# Schematico.net
KiCad netlist of a schematic drawn in EAGLE
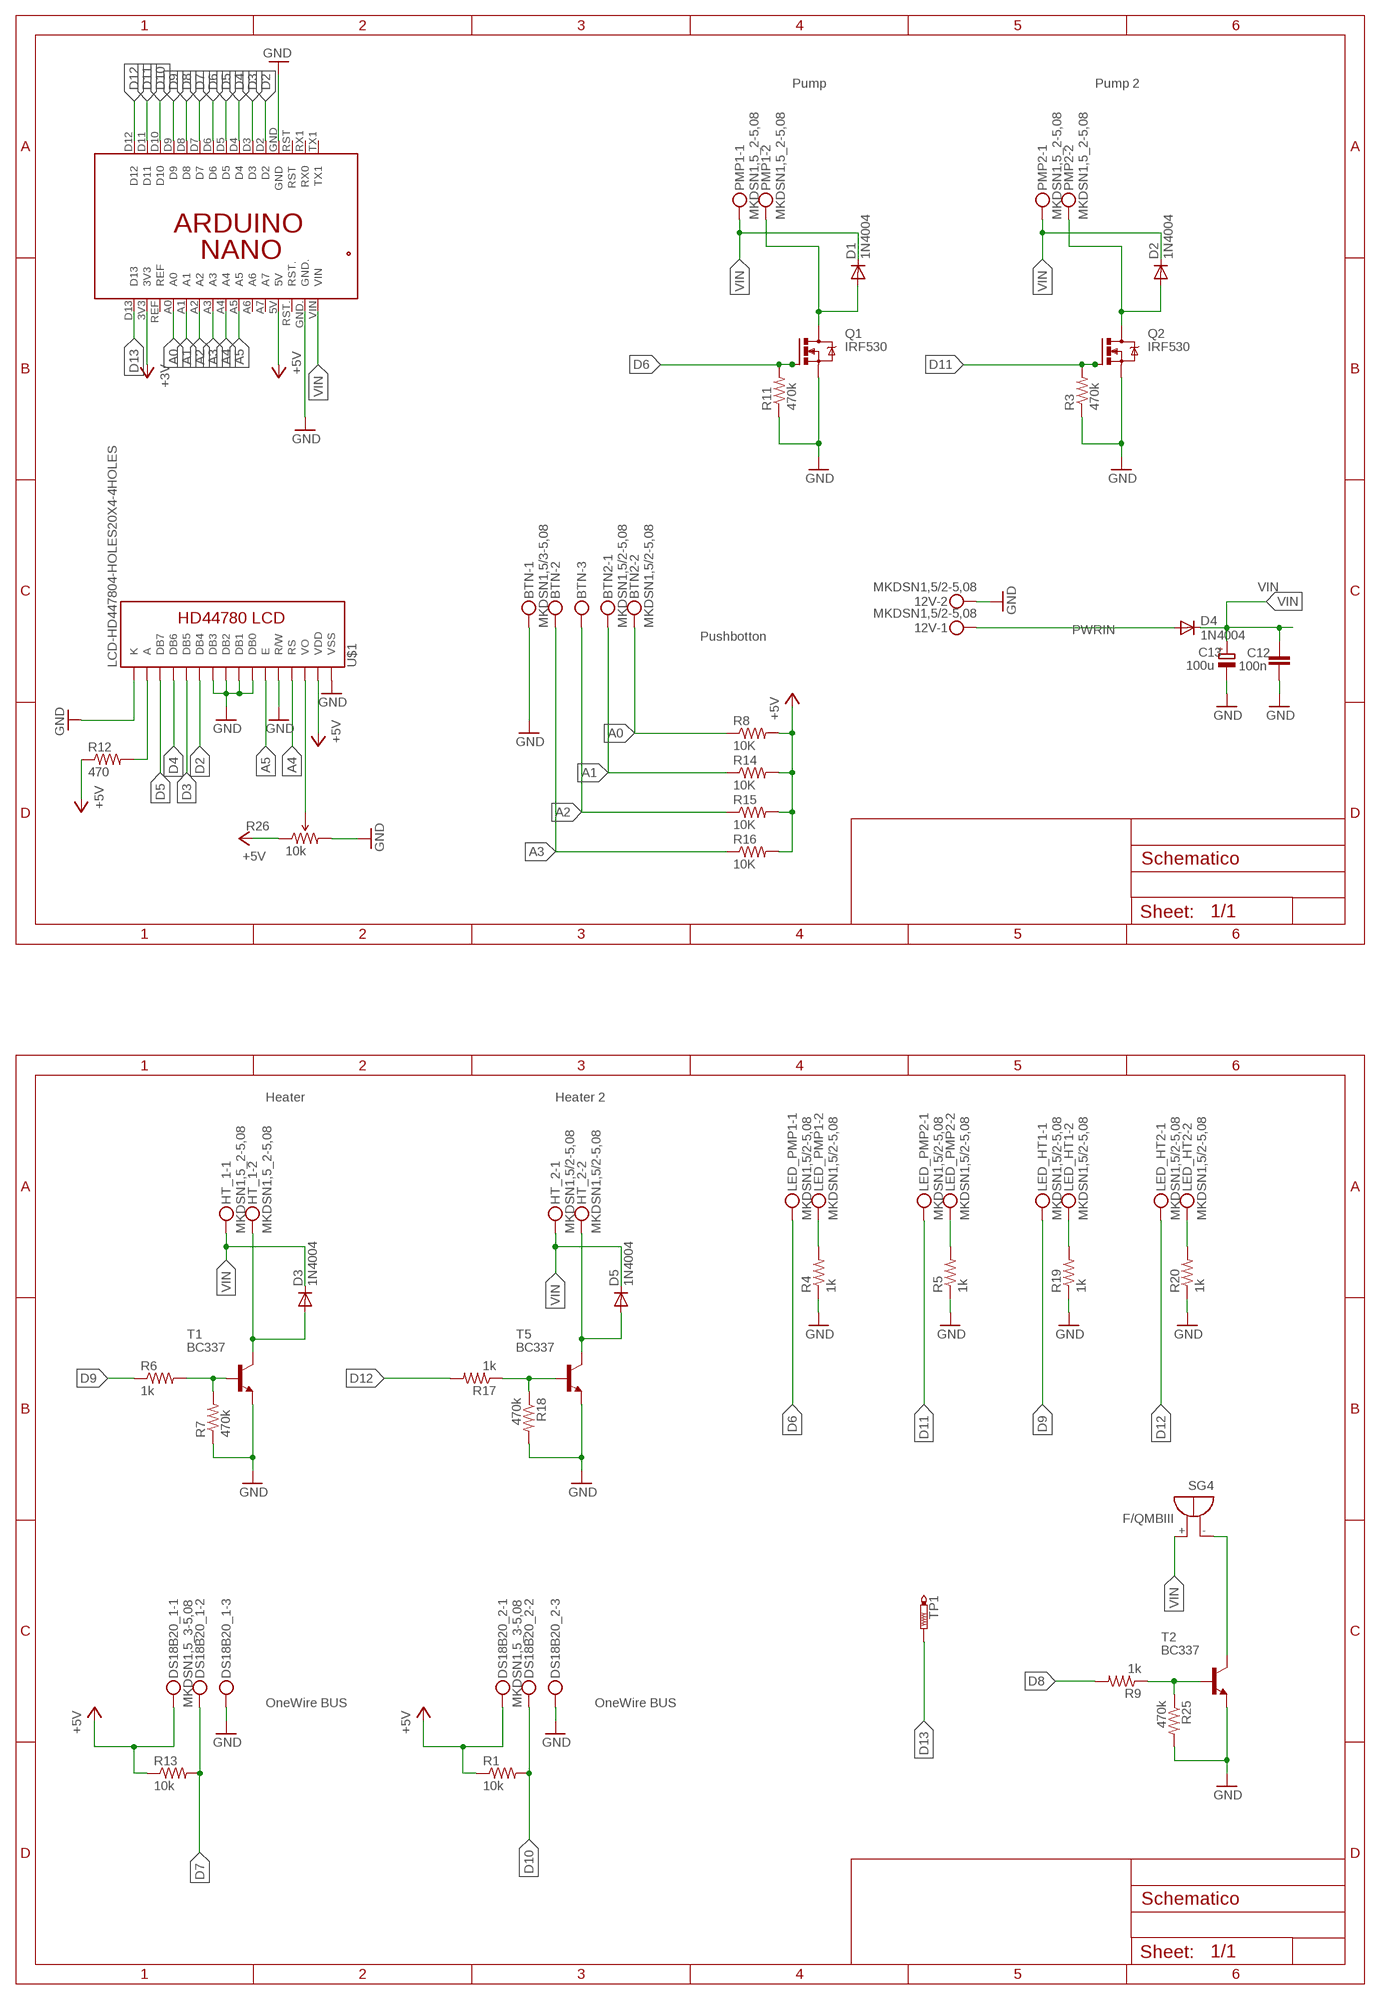
[diagram p0: schematic, sheet 1]

(export (version "E")
  (design (tool "Eeschema 10.0.6"))
  (components
    (comp (ref "12V")
      (value "MKDSN1,5/2-5,08")
      (footprint "eagle-import:MKDSN1,5_2-5,08")
      (fields (field (name "OC_NEWARK") "unknown"))
      (libsource (lib "eagle-import") (part "MKDSN1,5/2-5,08"))
    )
    (comp (ref "BTN")
      (value "MKDSN1,5/3-5,08")
      (footprint "eagle-import:MKDSN1,5_3-5,08")
      (fields (field (name "OC_NEWARK") "unknown"))
      (libsource (lib "eagle-import") (part "MKDSN1,5/3-5,08"))
    )
    (comp (ref "BTN2")
      (value "MKDSN1,5/2-5,08")
      (footprint "eagle-import:MKDSN1,5_2-5,08")
      (fields (field (name "OC_NEWARK") "unknown"))
      (libsource (lib "eagle-import") (part "MKDSN1,5/2-5,08"))
    )
    (comp (ref "C12")
      (value "100n")
      (footprint "eagle-import:C050-024X044")
      (libsource (lib "eagle-import") (part "C-EU050-024X044"))
    )
    (comp (ref "C13")
      (value "100u")
      (footprint "eagle-import:TT5D6")
      (libsource (lib "eagle-import") (part "CPOL-EUTT6D6"))
    )
    (comp (ref "D1")
      (value "1N4004")
      (footprint "eagle-import:DO41-10")
      (libsource (lib "eagle-import") (part "1N4004"))
    )
    (comp (ref "D2")
      (value "1N4004")
      (footprint "eagle-import:DO41-10")
      (libsource (lib "eagle-import") (part "1N4004"))
    )
    (comp (ref "D3")
      (value "1N4004")
      (footprint "eagle-import:DO41-10")
      (libsource (lib "eagle-import") (part "1N4004"))
    )
    (comp (ref "D4")
      (value "1N4004")
      (footprint "eagle-import:DO41-10")
      (libsource (lib "eagle-import") (part "1N4004"))
    )
    (comp (ref "D5")
      (value "1N4004")
      (footprint "eagle-import:DO41-10")
      (libsource (lib "eagle-import") (part "1N4004"))
    )
    (comp (ref "DS18B20_1")
      (value "MKDSN1,5_3-5,08")
      (footprint "eagle-import:MKDSN1,5-3-5,08")
      (fields (field (name "OC_NEWARK") "unknown"))
      (libsource (lib "eagle-import") (part "MKDSN1,5_3-5,08"))
    )
    (comp (ref "DS18B20_2")
      (value "MKDSN1,5_3-5,08")
      (footprint "eagle-import:MKDSN1,5-3-5,08")
      (fields (field (name "OC_NEWARK") "unknown"))
      (libsource (lib "eagle-import") (part "MKDSN1,5_3-5,08"))
    )
    (comp (ref "HT_1")
      (value "MKDSN1,5_2-5,08")
      (footprint "eagle-import:MKDSN1,5-2-5,08")
      (fields (field (name "OC_NEWARK") "unknown"))
      (libsource (lib "eagle-import") (part "MKDSN1,5_2-5,08"))
    )
    (comp (ref "HT_2")
      (value "MKDSN1,5/2-5,08")
      (footprint "eagle-import:MKDSN1,5_2-5,08")
      (libsource (lib "eagle-import") (part "MKDSN1,5/2-5,08"))
    )
    (comp (ref "LED_HT1")
      (value "MKDSN1,5/2-5,08")
      (footprint "eagle-import:MKDSN1,5_2-5,08")
      (libsource (lib "eagle-import") (part "MKDSN1,5/2-5,08"))
    )
    (comp (ref "LED_HT2")
      (value "MKDSN1,5/2-5,08")
      (footprint "eagle-import:MKDSN1,5_2-5,08")
      (libsource (lib "eagle-import") (part "MKDSN1,5/2-5,08"))
    )
    (comp (ref "LED_PMP1")
      (value "MKDSN1,5/2-5,08")
      (footprint "eagle-import:MKDSN1,5_2-5,08")
      (libsource (lib "eagle-import") (part "MKDSN1,5/2-5,08"))
    )
    (comp (ref "LED_PMP2")
      (value "MKDSN1,5/2-5,08")
      (footprint "eagle-import:MKDSN1,5_2-5,08")
      (libsource (lib "eagle-import") (part "MKDSN1,5/2-5,08"))
    )
    (comp (ref "PCB1")
      (value "ARDUINO_NANO")
      (footprint "eagle-import:ARDUINO_NANO")
      (libsource (lib "eagle-import") (part "ARDUINO_NANO"))
    )
    (comp (ref "PMP1")
      (value "MKDSN1,5_2-5,08")
      (footprint "eagle-import:MKDSN1,5-2-5,08")
      (fields (field (name "OC_NEWARK") "unknown"))
      (libsource (lib "eagle-import") (part "MKDSN1,5_2-5,08"))
    )
    (comp (ref "PMP2")
      (value "MKDSN1,5_2-5,08")
      (footprint "eagle-import:MKDSN1,5-2-5,08")
      (fields (field (name "OC_NEWARK") "unknown"))
      (libsource (lib "eagle-import") (part "MKDSN1,5_2-5,08"))
    )
    (comp (ref "Q1")
      (value "IRF530")
      (footprint "eagle-import:TO220BV")
      (libsource (lib "eagle-import") (part "IRF530"))
    )
    (comp (ref "Q2")
      (value "IRF530")
      (footprint "eagle-import:TO220BV")
      (libsource (lib "eagle-import") (part "IRF530"))
    )
    (comp (ref "R1")
      (value "10k")
      (footprint "eagle-import:0207_10")
      (libsource (lib "eagle-import") (part "R-US_0207/10"))
    )
    (comp (ref "R3")
      (value "470k")
      (footprint "eagle-import:0207_10")
      (libsource (lib "eagle-import") (part "R-US_0207/10"))
    )
    (comp (ref "R4")
      (value "1k")
      (footprint "eagle-import:0207_10")
      (libsource (lib "eagle-import") (part "R-US_0207/10"))
    )
    (comp (ref "R5")
      (value "1k")
      (footprint "eagle-import:0207_10")
      (libsource (lib "eagle-import") (part "R-US_0207/10"))
    )
    (comp (ref "R6")
      (value "1k")
      (footprint "eagle-import:0207_10")
      (libsource (lib "eagle-import") (part "R-US_0207/10"))
    )
    (comp (ref "R7")
      (value "470k")
      (footprint "eagle-import:0207_10")
      (libsource (lib "eagle-import") (part "R-US_0207/10"))
    )
    (comp (ref "R8")
      (value "10K")
      (footprint "eagle-import:0207_10")
      (libsource (lib "eagle-import") (part "R-US_0207/10"))
    )
    (comp (ref "R9")
      (value "1k")
      (footprint "eagle-import:0207_10")
      (libsource (lib "eagle-import") (part "R-US_0207/10"))
    )
    (comp (ref "R11")
      (value "470k")
      (footprint "eagle-import:0207_10")
      (libsource (lib "eagle-import") (part "R-US_0207/10"))
    )
    (comp (ref "R12")
      (value "470")
      (footprint "eagle-import:0207_10")
      (libsource (lib "eagle-import") (part "R-US_0207/10"))
    )
    (comp (ref "R13")
      (value "10k")
      (footprint "eagle-import:0207_10")
      (libsource (lib "eagle-import") (part "R-US_0207/10"))
    )
    (comp (ref "R14")
      (value "10K")
      (footprint "eagle-import:0207_10")
      (libsource (lib "eagle-import") (part "R-US_0207/10"))
    )
    (comp (ref "R15")
      (value "10K")
      (footprint "eagle-import:0207_10")
      (libsource (lib "eagle-import") (part "R-US_0207/10"))
    )
    (comp (ref "R16")
      (value "10K")
      (footprint "eagle-import:0207_10")
      (libsource (lib "eagle-import") (part "R-US_0207/10"))
    )
    (comp (ref "R17")
      (value "1k")
      (footprint "eagle-import:0207_10")
      (libsource (lib "eagle-import") (part "R-US_0207/10"))
    )
    (comp (ref "R18")
      (value "470k")
      (footprint "eagle-import:0207_10")
      (libsource (lib "eagle-import") (part "R-US_0207/10"))
    )
    (comp (ref "R19")
      (value "1k")
      (footprint "eagle-import:0207_10")
      (libsource (lib "eagle-import") (part "R-US_0207/10"))
    )
    (comp (ref "R20")
      (value "1k")
      (footprint "eagle-import:0207_10")
      (libsource (lib "eagle-import") (part "R-US_0207/10"))
    )
    (comp (ref "R25")
      (value "470k")
      (footprint "eagle-import:0207_10")
      (libsource (lib "eagle-import") (part "R-US_0207/10"))
    )
    (comp (ref "R26")
      (value "10k")
      (footprint "eagle-import:3362U-2")
      (libsource (lib "eagle-import") (part "TRIMPOT3362U-2"))
    )
    (comp (ref "SG4")
      (value "F/QMBIII")
      (footprint "eagle-import:F_QMBIII")
      (libsource (lib "eagle-import") (part "F/QMBIII"))
    )
    (comp (ref "T1")
      (value "BC337")
      (footprint "eagle-import:TO92")
      (libsource (lib "eagle-import") (part "BC337"))
    )
    (comp (ref "T2")
      (value "BC337")
      (footprint "eagle-import:TO92")
      (libsource (lib "eagle-import") (part "BC337"))
    )
    (comp (ref "T5")
      (value "BC337")
      (footprint "eagle-import:TO92")
      (libsource (lib "eagle-import") (part "BC337"))
    )
    (comp (ref "TP1")
      (value "PTR1PAD1-20")
      (footprint "eagle-import:P1-20")
      (libsource (lib "eagle-import") (part "PTR1PAD1-20"))
    )
    (comp (ref "U$1")
      (value "LCD-HD447804-HOLES20X4-4HOLES")
      (footprint "eagle-import:LCD-20X4-4HOLES")
      (libsource (lib "eagle-import") (part "LCD-HD4478020X4-4HOLES4-HOLES"))
    )
  )
  (nets
    (net (code "1") (name "+3V") (class "Default")
      (node (ref "PCB1") (pin "3V3") (pinfunction "3V3_3V3") (pintype "bidirectional"))
    )
    (net (code "2") (name "+5V") (class "Default")
      (node (ref "DS18B20_1") (pin "1") (pinfunction "KL_1") (pintype "passive"))
      (node (ref "DS18B20_2") (pin "1") (pinfunction "KL_1") (pintype "passive"))
      (node (ref "PCB1") (pin "5V") (pinfunction "5V_5V") (pintype "bidirectional"))
      (node (ref "R1") (pin "1") (pinfunction "1_1") (pintype "passive"))
      (node (ref "R12") (pin "1") (pinfunction "1_1") (pintype "passive"))
      (node (ref "R13") (pin "1") (pinfunction "1_1") (pintype "passive"))
      (node (ref "R14") (pin "2") (pinfunction "2_2") (pintype "passive"))
      (node (ref "R15") (pin "2") (pinfunction "2_2") (pintype "passive"))
      (node (ref "R16") (pin "2") (pinfunction "2_2") (pintype "passive"))
      (node (ref "R26") (pin "1") (pinfunction "CCW_1") (pintype "passive"))
      (node (ref "R8") (pin "2") (pinfunction "2_2") (pintype "passive"))
      (node (ref "U$1") (pin "P$2") (pinfunction "VDD_P$2") (pintype "power_in"))
    )
    (net (code "3") (name "/PWRIN") (class "Default")
      (node (ref "12V") (pin "1") (pinfunction "KL_1") (pintype "passive"))
      (node (ref "D4") (pin "A") (pinfunction "A_A") (pintype "passive"))
    )
    (net (code "4") (name "A0") (class "Default")
      (node (ref "BTN2") (pin "2") (pinfunction "KL_2") (pintype "passive"))
      (node (ref "PCB1") (pin "A0") (pinfunction "A0_A0") (pintype "bidirectional"))
      (node (ref "R8") (pin "1") (pinfunction "1_1") (pintype "passive"))
    )
    (net (code "5") (name "A1") (class "Default")
      (node (ref "BTN2") (pin "1") (pinfunction "KL_1") (pintype "passive"))
      (node (ref "PCB1") (pin "A1") (pinfunction "A1_A1") (pintype "bidirectional"))
      (node (ref "R14") (pin "1") (pinfunction "1_1") (pintype "passive"))
    )
    (net (code "6") (name "A2") (class "Default")
      (node (ref "BTN") (pin "3") (pinfunction "KL_3") (pintype "passive"))
      (node (ref "PCB1") (pin "A2") (pinfunction "A2_A2") (pintype "bidirectional"))
      (node (ref "R15") (pin "1") (pinfunction "1_1") (pintype "passive"))
    )
    (net (code "7") (name "A3") (class "Default")
      (node (ref "BTN") (pin "2") (pinfunction "KL_2") (pintype "passive"))
      (node (ref "PCB1") (pin "A3") (pinfunction "A3_A3") (pintype "bidirectional"))
      (node (ref "R16") (pin "1") (pinfunction "1_1") (pintype "passive"))
    )
    (net (code "8") (name "A4") (class "Default")
      (node (ref "PCB1") (pin "A4") (pinfunction "A4_A4") (pintype "bidirectional"))
      (node (ref "U$1") (pin "P$4") (pinfunction "RS_P$4") (pintype "input"))
    )
    (net (code "9") (name "A5") (class "Default")
      (node (ref "PCB1") (pin "A5") (pinfunction "A5_A5") (pintype "bidirectional"))
      (node (ref "U$1") (pin "P$6") (pinfunction "E_P$6") (pintype "input"))
    )
    (net (code "10") (name "D2") (class "Default")
      (node (ref "PCB1") (pin "D2") (pinfunction "D2_D2") (pintype "bidirectional"))
      (node (ref "U$1") (pin "P$11") (pinfunction "DB4_P$11") (pintype "bidirectional"))
    )
    (net (code "11") (name "D3") (class "Default")
      (node (ref "PCB1") (pin "D3") (pinfunction "D3_D3") (pintype "bidirectional"))
      (node (ref "U$1") (pin "P$12") (pinfunction "DB5_P$12") (pintype "bidirectional"))
    )
    (net (code "12") (name "D4") (class "Default")
      (node (ref "PCB1") (pin "D4") (pinfunction "D4_D4") (pintype "bidirectional"))
      (node (ref "U$1") (pin "P$13") (pinfunction "DB6_P$13") (pintype "bidirectional"))
    )
    (net (code "13") (name "D5") (class "Default")
      (node (ref "PCB1") (pin "D5") (pinfunction "D5_D5") (pintype "bidirectional"))
      (node (ref "U$1") (pin "P$14") (pinfunction "DB7_P$14") (pintype "bidirectional"))
    )
    (net (code "14") (name "D6") (class "Default")
      (node (ref "LED_PMP1") (pin "1") (pinfunction "KL_1") (pintype "passive"))
      (node (ref "PCB1") (pin "D6") (pinfunction "D6_D6") (pintype "bidirectional"))
      (node (ref "Q1") (pin "G") (pinfunction "G_G") (pintype "passive"))
      (node (ref "R11") (pin "2") (pinfunction "2_2") (pintype "passive"))
    )
    (net (code "15") (name "D7") (class "Default")
      (node (ref "DS18B20_1") (pin "2") (pinfunction "KL_2") (pintype "passive"))
      (node (ref "PCB1") (pin "D7") (pinfunction "D7_D7") (pintype "bidirectional"))
      (node (ref "R13") (pin "2") (pinfunction "2_2") (pintype "passive"))
    )
    (net (code "16") (name "D8") (class "Default")
      (node (ref "PCB1") (pin "D8") (pinfunction "D8_D8") (pintype "bidirectional"))
      (node (ref "R9") (pin "2") (pinfunction "2_2") (pintype "passive"))
    )
    (net (code "17") (name "D9") (class "Default")
      (node (ref "LED_HT1") (pin "1") (pinfunction "KL_1") (pintype "passive"))
      (node (ref "PCB1") (pin "D9") (pinfunction "D9_D9") (pintype "bidirectional"))
      (node (ref "R6") (pin "1") (pinfunction "1_1") (pintype "passive"))
    )
    (net (code "18") (name "D10") (class "Default")
      (node (ref "DS18B20_2") (pin "2") (pinfunction "KL_2") (pintype "passive"))
      (node (ref "PCB1") (pin "D10") (pinfunction "D10_D10") (pintype "bidirectional"))
      (node (ref "R1") (pin "2") (pinfunction "2_2") (pintype "passive"))
    )
    (net (code "19") (name "D11") (class "Default")
      (node (ref "LED_PMP2") (pin "1") (pinfunction "KL_1") (pintype "passive"))
      (node (ref "PCB1") (pin "D11") (pinfunction "D11_D11") (pintype "bidirectional"))
      (node (ref "Q2") (pin "G") (pinfunction "G_G") (pintype "passive"))
      (node (ref "R3") (pin "2") (pinfunction "2_2") (pintype "passive"))
    )
    (net (code "20") (name "D12") (class "Default")
      (node (ref "LED_HT2") (pin "1") (pinfunction "KL_1") (pintype "passive"))
      (node (ref "PCB1") (pin "D12") (pinfunction "D12_D12") (pintype "bidirectional"))
      (node (ref "R17") (pin "2") (pinfunction "2_2") (pintype "passive"))
    )
    (net (code "21") (name "D13") (class "Default")
      (node (ref "PCB1") (pin "D13") (pinfunction "D13_D13") (pintype "bidirectional"))
      (node (ref "TP1") (pin "TP") (pinfunction "TP_TP") (pintype "input"))
    )
    (net (code "22") (name "GND") (class "Default")
      (node (ref "12V") (pin "2") (pinfunction "KL_2") (pintype "passive"))
      (node (ref "BTN") (pin "1") (pinfunction "KL_1") (pintype "passive"))
      (node (ref "C12") (pin "1") (pinfunction "1_1") (pintype "passive"))
      (node (ref "C13") (pin "-") (pinfunction "-_-") (pintype "passive"))
      (node (ref "DS18B20_1") (pin "3") (pinfunction "KL_3") (pintype "passive"))
      (node (ref "DS18B20_2") (pin "3") (pinfunction "KL_3") (pintype "passive"))
      (node (ref "PCB1") (pin "GND") (pinfunction "GND_GND") (pintype "bidirectional"))
      (node (ref "PCB1") (pin "GND.") (pinfunction "GND._GND.") (pintype "bidirectional"))
      (node (ref "Q1") (pin "S") (pinfunction "S_S") (pintype "passive"))
      (node (ref "Q2") (pin "S") (pinfunction "S_S") (pintype "passive"))
      (node (ref "R11") (pin "1") (pinfunction "1_1") (pintype "passive"))
      (node (ref "R18") (pin "2") (pinfunction "2_2") (pintype "passive"))
      (node (ref "R19") (pin "1") (pinfunction "1_1") (pintype "passive"))
      (node (ref "R20") (pin "1") (pinfunction "1_1") (pintype "passive"))
      (node (ref "R25") (pin "2") (pinfunction "2_2") (pintype "passive"))
      (node (ref "R26") (pin "3") (pinfunction "CW_3") (pintype "passive"))
      (node (ref "R3") (pin "1") (pinfunction "1_1") (pintype "passive"))
      (node (ref "R4") (pin "1") (pinfunction "1_1") (pintype "passive"))
      (node (ref "R5") (pin "1") (pinfunction "1_1") (pintype "passive"))
      (node (ref "R7") (pin "1") (pinfunction "1_1") (pintype "passive"))
      (node (ref "T1") (pin "1") (pinfunction "E_1") (pintype "passive"))
      (node (ref "T2") (pin "1") (pinfunction "E_1") (pintype "passive"))
      (node (ref "T5") (pin "1") (pinfunction "E_1") (pintype "passive"))
      (node (ref "U$1") (pin "P$1") (pinfunction "VSS_P$1") (pintype "power_in"))
      (node (ref "U$1") (pin "P$10") (pinfunction "DB3_P$10") (pintype "bidirectional"))
      (node (ref "U$1") (pin "P$16") (pinfunction "K_P$16") (pintype "power_in"))
      (node (ref "U$1") (pin "P$5") (pinfunction "R/W_P$5") (pintype "input"))
      (node (ref "U$1") (pin "P$7") (pinfunction "DB0_P$7") (pintype "bidirectional"))
      (node (ref "U$1") (pin "P$8") (pinfunction "DB1_P$8") (pintype "bidirectional"))
      (node (ref "U$1") (pin "P$9") (pinfunction "DB2_P$9") (pintype "bidirectional"))
    )
    (net (code "23") (name "Net-(HT_1B-KL)") (class "Default")
      (node (ref "D3") (pin "A") (pinfunction "A_A") (pintype "passive"))
      (node (ref "HT_1") (pin "2") (pinfunction "KL_2") (pintype "passive"))
      (node (ref "T1") (pin "3") (pinfunction "C_3") (pintype "passive"))
    )
    (net (code "24") (name "Net-(HT_2B-KL)") (class "Default")
      (node (ref "D5") (pin "A") (pinfunction "A_A") (pintype "passive"))
      (node (ref "HT_2") (pin "2") (pinfunction "KL_2") (pintype "passive"))
      (node (ref "T5") (pin "3") (pinfunction "C_3") (pintype "passive"))
    )
    (net (code "25") (name "Net-(LED_HT1B-KL)") (class "Default")
      (node (ref "LED_HT1") (pin "2") (pinfunction "KL_2") (pintype "passive"))
      (node (ref "R19") (pin "2") (pinfunction "2_2") (pintype "passive"))
    )
    (net (code "26") (name "Net-(LED_HT2B-KL)") (class "Default")
      (node (ref "LED_HT2") (pin "2") (pinfunction "KL_2") (pintype "passive"))
      (node (ref "R20") (pin "2") (pinfunction "2_2") (pintype "passive"))
    )
    (net (code "27") (name "Net-(LED_PMP1B-KL)") (class "Default")
      (node (ref "LED_PMP1") (pin "2") (pinfunction "KL_2") (pintype "passive"))
      (node (ref "R4") (pin "2") (pinfunction "2_2") (pintype "passive"))
    )
    (net (code "28") (name "Net-(LED_PMP2B-KL)") (class "Default")
      (node (ref "LED_PMP2") (pin "2") (pinfunction "KL_2") (pintype "passive"))
      (node (ref "R5") (pin "2") (pinfunction "2_2") (pintype "passive"))
    )
    (net (code "29") (name "Net-(PMP1B-KL)") (class "Default")
      (node (ref "D1") (pin "A") (pinfunction "A_A") (pintype "passive"))
      (node (ref "PMP1") (pin "2") (pinfunction "KL_2") (pintype "passive"))
      (node (ref "Q1") (pin "D") (pinfunction "D_D") (pintype "passive"))
    )
    (net (code "30") (name "Net-(PMP2B-KL)") (class "Default")
      (node (ref "D2") (pin "A") (pinfunction "A_A") (pintype "passive"))
      (node (ref "PMP2") (pin "2") (pinfunction "KL_2") (pintype "passive"))
      (node (ref "Q2") (pin "D") (pinfunction "D_D") (pintype "passive"))
    )
    (net (code "31") (name "Net-(R26-WIPER)") (class "Default")
      (node (ref "R26") (pin "2") (pinfunction "WIPER_2") (pintype "passive"))
      (node (ref "U$1") (pin "P$3") (pinfunction "VO_P$3") (pintype "bidirectional"))
    )
    (net (code "32") (name "Net-(SG4-+)") (class "Default")
      (node (ref "SG4") (pin "-") (pinfunction "+_-") (pintype "passive"))
      (node (ref "T2") (pin "3") (pinfunction "C_3") (pintype "passive"))
    )
    (net (code "33") (name "Net-(T1-B)") (class "Default")
      (node (ref "R6") (pin "2") (pinfunction "2_2") (pintype "passive"))
      (node (ref "R7") (pin "2") (pinfunction "2_2") (pintype "passive"))
      (node (ref "T1") (pin "2") (pinfunction "B_2") (pintype "passive"))
    )
    (net (code "34") (name "Net-(T2-B)") (class "Default")
      (node (ref "R25") (pin "1") (pinfunction "1_1") (pintype "passive"))
      (node (ref "R9") (pin "1") (pinfunction "1_1") (pintype "passive"))
      (node (ref "T2") (pin "2") (pinfunction "B_2") (pintype "passive"))
    )
    (net (code "35") (name "Net-(T5-B)") (class "Default")
      (node (ref "R17") (pin "1") (pinfunction "1_1") (pintype "passive"))
      (node (ref "R18") (pin "1") (pinfunction "1_1") (pintype "passive"))
      (node (ref "T5") (pin "2") (pinfunction "B_2") (pintype "passive"))
    )
    (net (code "36") (name "Net-(U$1-A)") (class "Default")
      (node (ref "R12") (pin "2") (pinfunction "2_2") (pintype "passive"))
      (node (ref "U$1") (pin "P$15") (pinfunction "A_P$15") (pintype "power_in"))
    )
    (net (code "37") (name "VIN") (class "Default")
      (node (ref "C12") (pin "2") (pinfunction "2_2") (pintype "passive"))
      (node (ref "C13") (pin "+") (pinfunction "+_+") (pintype "passive"))
      (node (ref "D1") (pin "C") (pinfunction "C_C") (pintype "passive"))
      (node (ref "D2") (pin "C") (pinfunction "C_C") (pintype "passive"))
      (node (ref "D3") (pin "C") (pinfunction "C_C") (pintype "passive"))
      (node (ref "D4") (pin "C") (pinfunction "C_C") (pintype "passive"))
      (node (ref "D5") (pin "C") (pinfunction "C_C") (pintype "passive"))
      (node (ref "HT_1") (pin "1") (pinfunction "KL_1") (pintype "passive"))
      (node (ref "HT_2") (pin "1") (pinfunction "KL_1") (pintype "passive"))
      (node (ref "PCB1") (pin "VIN") (pinfunction "VIN_VIN") (pintype "bidirectional"))
      (node (ref "PMP1") (pin "1") (pinfunction "KL_1") (pintype "passive"))
      (node (ref "PMP2") (pin "1") (pinfunction "KL_1") (pintype "passive"))
      (node (ref "SG4") (pin "+") (pinfunction "-_+") (pintype "passive"))
    )
    (net (code "38") (name "unconnected-(PCB1-PadA6)") (class "Default")
      (node (ref "PCB1") (pin "A6") (pinfunction "A6_A6") (pintype "bidirectional"))
    )
    (net (code "39") (name "unconnected-(PCB1-PadA7)") (class "Default")
      (node (ref "PCB1") (pin "A7") (pinfunction "A7_A7") (pintype "bidirectional"))
    )
    (net (code "40") (name "unconnected-(PCB1-PadREF)") (class "Default")
      (node (ref "PCB1") (pin "REF") (pinfunction "REF_REF") (pintype "bidirectional"))
    )
    (net (code "41") (name "unconnected-(PCB1-PadRST)") (class "Default")
      (node (ref "PCB1") (pin "RST") (pinfunction "RST_RST") (pintype "bidirectional"))
    )
    (net (code "42") (name "unconnected-(PCB1-PadRST.)") (class "Default")
      (node (ref "PCB1") (pin "RST.") (pinfunction "RST._RST.") (pintype "bidirectional"))
    )
    (net (code "43") (name "unconnected-(PCB1-PadTX1)") (class "Default")
      (node (ref "PCB1") (pin "TX1") (pinfunction "TX1_TX1") (pintype "bidirectional"))
    )
    (net (code "44") (name "unconnected-(PCB1-RX0-PadRX1)") (class "Default")
      (node (ref "PCB1") (pin "RX1") (pinfunction "RX0_RX1") (pintype "bidirectional"))
    )
  )
)
